# optic_fiber.net
KiCad netlist of a schematic drawn in Altium Designer
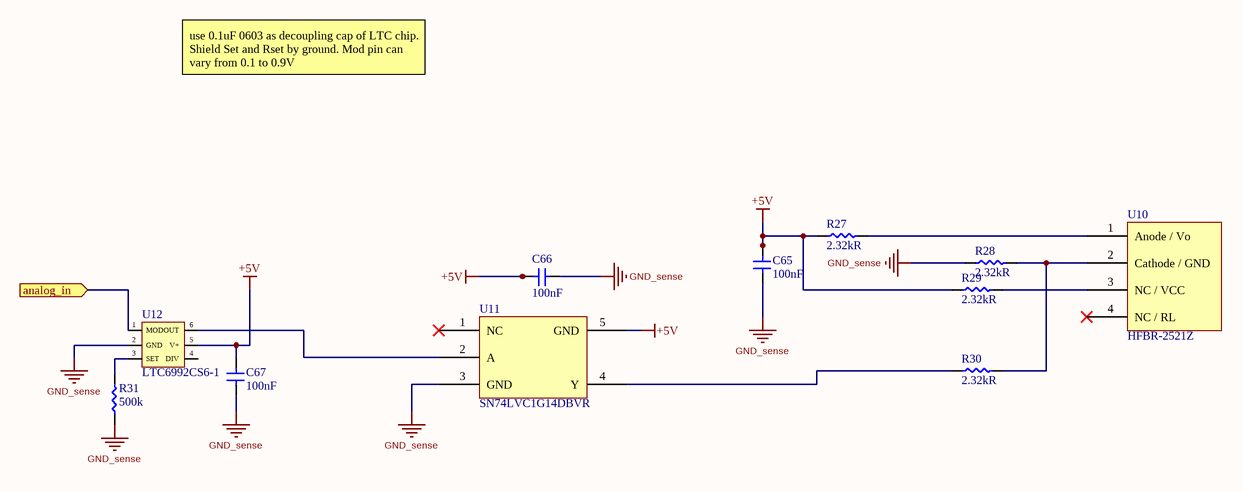
[diagram p0: optic_fiber.SchDoc]

(export (version "E")
  (design (tool "Eeschema 10.0.6"))
  (components
    (comp (ref "C65")
      (value "100nF")
      (footprint "C0603")
      (description "CAP CER 0.1UF 50V Y5V 0603")
      (fields
        (field (name "MANUFACTURER") "Kyocera AVX")
        (field (name "MANUFACTURER PART NUMBER") "06035G104ZAT2A")
      )
      (libsource (lib "24_12_buck") (part "06035G104ZAT2A"))
    )
    (comp (ref "C66")
      (value "100nF")
      (footprint "C0603")
      (description "CAP CER 0.1UF 50V Y5V 0603")
      (fields
        (field (name "MANUFACTURER") "Kyocera AVX")
        (field (name "MANUFACTURER PART NUMBER") "06035G104ZAT2A")
      )
      (libsource (lib "24_12_buck") (part "06035G104ZAT2A"))
    )
    (comp (ref "C67")
      (value "100nF")
      (footprint "C0603")
      (description "CAP CER 0.1UF 50V Y5V 0603")
      (fields
        (field (name "MANUFACTURER") "Kyocera AVX")
        (field (name "MANUFACTURER PART NUMBER") "06035G104ZAT2A")
      )
      (libsource (lib "24_12_buck") (part "06035G104ZAT2A"))
    )
    (comp (ref "R27")
      (value "2.32kR")
      (footprint "R0603")
      (fields
        (field (name "MANUFACTURER") "Panasonic")
        (field (name "MANUFACTURER PART NUMBER") "ERA-3AEB2321V")
        (field (name "TOLERANCE") "0.1%")
      )
      (libsource (lib "24_12_buck") (part "ERA-3AEB2321V"))
    )
    (comp (ref "R28")
      (value "2.32kR")
      (footprint "R0603")
      (fields
        (field (name "MANUFACTURER") "Panasonic")
        (field (name "MANUFACTURER PART NUMBER") "ERA-3AEB2321V")
        (field (name "TOLERANCE") "0.1%")
      )
      (libsource (lib "24_12_buck") (part "ERA-3AEB2321V"))
    )
    (comp (ref "R29")
      (value "2.32kR")
      (footprint "R0603")
      (fields
        (field (name "MANUFACTURER") "Panasonic")
        (field (name "MANUFACTURER PART NUMBER") "ERA-3AEB2321V")
        (field (name "TOLERANCE") "0.1%")
      )
      (libsource (lib "24_12_buck") (part "ERA-3AEB2321V"))
    )
    (comp (ref "R30")
      (value "2.32kR")
      (footprint "R0603")
      (fields
        (field (name "MANUFACTURER") "Panasonic")
        (field (name "MANUFACTURER PART NUMBER") "ERA-3AEB2321V")
        (field (name "TOLERANCE") "0.1%")
      )
      (libsource (lib "24_12_buck") (part "ERA-3AEB2321V"))
    )
    (comp (ref "R31")
      (value "500k")
      (footprint "R0603")
      (fields
        (field (name "MANUFACTURER") "Panasonic")
        (field (name "MANUFACTURER PART NUMBER") "ERA-3AEB2321V")
        (field (name "TOLERANCE") "0.1%")
      )
      (libsource (lib "24_12_buck") (part "ERA-3AEB2321V"))
    )
    (comp (ref "U10")
      (value "HFBR-2521Z")
      (footprint "HFBR")
      (description "AVAGO TECHNOLOGIES   HFBR-2521Z   FIBRE OPTIC, RECEIVER, 5MBD")
      (fields (field (name "MANUFACTURER") "Broadcom Avago"))
      (libsource (lib "Connector") (part "HFBR-2521Z"))
    )
    (comp (ref "U11")
      (value "SN74LVC1G14DBVR")
      (footprint "SOT23-5")
      (description "IC INVERTER SCHMITT 1CH SOT23-5")
      (fields (field (name "MANUFACTURER") "Texas Instruments"))
      (libsource (lib "ActiveComp") (part "SN74LVC1G14DBVR"))
    )
    (comp (ref "U12")
      (value "LTC6992CS6-1")
      (footprint "SOT23-6_proper")
      (description "LINEAR TECHNOLOGY   LTC6992CS6-1#TRMPBF   PWM, VOLT CTRL, TIMERBLOX, 6SOT-23")
      (fields
        (field (name "MANUFACTURER") "Analog Devices / Linear Technology")
        (field (name "MANUFACTURER PART NUMBER") "LTC6992CS6-1#TRMPBF")
      )
      (libsource (lib "current_sense") (part "LTC6992CS6-1#TRMPBF"))
    )
  )
  (nets
    (net (code "1") (name "+5V") (class "Default")
      (node (ref "C65") (pin "2") (pinfunction "2_2") (pintype "passive"))
      (node (ref "C66") (pin "2") (pinfunction "2_2") (pintype "passive"))
      (node (ref "C67") (pin "2") (pinfunction "2_2") (pintype "passive"))
      (node (ref "R27") (pin "1") (pinfunction "3_1") (pintype "passive"))
      (node (ref "R29") (pin "1") (pinfunction "3_1") (pintype "passive"))
      (node (ref "U11") (pin "5") (pinfunction "GND_5") (pintype "passive"))
      (node (ref "U12") (pin "5") (pinfunction "V+_5") (pintype "power_in"))
    )
    (net (code "2") (name "/analog_in") (class "Default")
      (node (ref "U12") (pin "1") (pinfunction "MOD_1") (pintype "power_in"))
    )
    (net (code "3") (name "GND_sense") (class "Default")
      (node (ref "C65") (pin "1") (pinfunction "1_1") (pintype "passive"))
      (node (ref "C66") (pin "1") (pinfunction "1_1") (pintype "passive"))
      (node (ref "C67") (pin "1") (pinfunction "1_1") (pintype "passive"))
      (node (ref "R28") (pin "1") (pinfunction "3_1") (pintype "passive"))
      (node (ref "R31") (pin "1") (pinfunction "3_1") (pintype "passive"))
      (node (ref "U11") (pin "3") (pinfunction "GND_3") (pintype "passive"))
      (node (ref "U12") (pin "2") (pinfunction "GND_2") (pintype "power_in"))
    )
    (net (code "4") (name "Net-(R27-4)") (class "Default")
      (node (ref "R27") (pin "2") (pinfunction "4_2") (pintype "passive"))
      (node (ref "U10") (pin "1") (pinfunction "Anode_/_Vo_1") (pintype "passive"))
    )
    (net (code "5") (name "Net-(R28-4)") (class "Default")
      (node (ref "R28") (pin "2") (pinfunction "4_2") (pintype "passive"))
      (node (ref "R30") (pin "2") (pinfunction "4_2") (pintype "passive"))
      (node (ref "U10") (pin "2") (pinfunction "Cathode_/_GND_2") (pintype "passive"))
    )
    (net (code "6") (name "Net-(R29-4)") (class "Default")
      (node (ref "R29") (pin "2") (pinfunction "4_2") (pintype "passive"))
      (node (ref "U10") (pin "3") (pinfunction "NC_/_VCC_3") (pintype "passive"))
    )
    (net (code "7") (name "Net-(R30-3)") (class "Default")
      (node (ref "R30") (pin "1") (pinfunction "3_1") (pintype "passive"))
      (node (ref "U11") (pin "4") (pinfunction "Y_4") (pintype "passive"))
    )
    (net (code "8") (name "Net-(R31-4)") (class "Default")
      (node (ref "R31") (pin "2") (pinfunction "4_2") (pintype "passive"))
      (node (ref "U12") (pin "3") (pinfunction "SET_3") (pintype "power_in"))
    )
    (net (code "9") (name "Net-(U11-A)") (class "Default")
      (node (ref "U11") (pin "2") (pinfunction "A_2") (pintype "passive"))
      (node (ref "U12") (pin "6") (pinfunction "OUT_6") (pintype "power_in"))
    )
    (net (code "10") (name "unconnected-(U10-NC_{slash}_RL-Pad4)") (class "Default")
      (node (ref "U10") (pin "4") (pinfunction "NC_/_RL_4") (pintype "passive+no_connect"))
    )
    (net (code "11") (name "unconnected-(U11-NC-Pad1)") (class "Default")
      (node (ref "U11") (pin "1") (pinfunction "NC_1") (pintype "passive+no_connect"))
    )
    (net (code "12") (name "unconnected-(U12-DIV-Pad4)") (class "Default")
      (node (ref "U12") (pin "4") (pinfunction "DIV_4") (pintype "power_in"))
    )
  )
)
